# SCH_CANSAT-AD_K_2025-02-23.net
KiCad netlist of a schematic drawn in EasyEDA
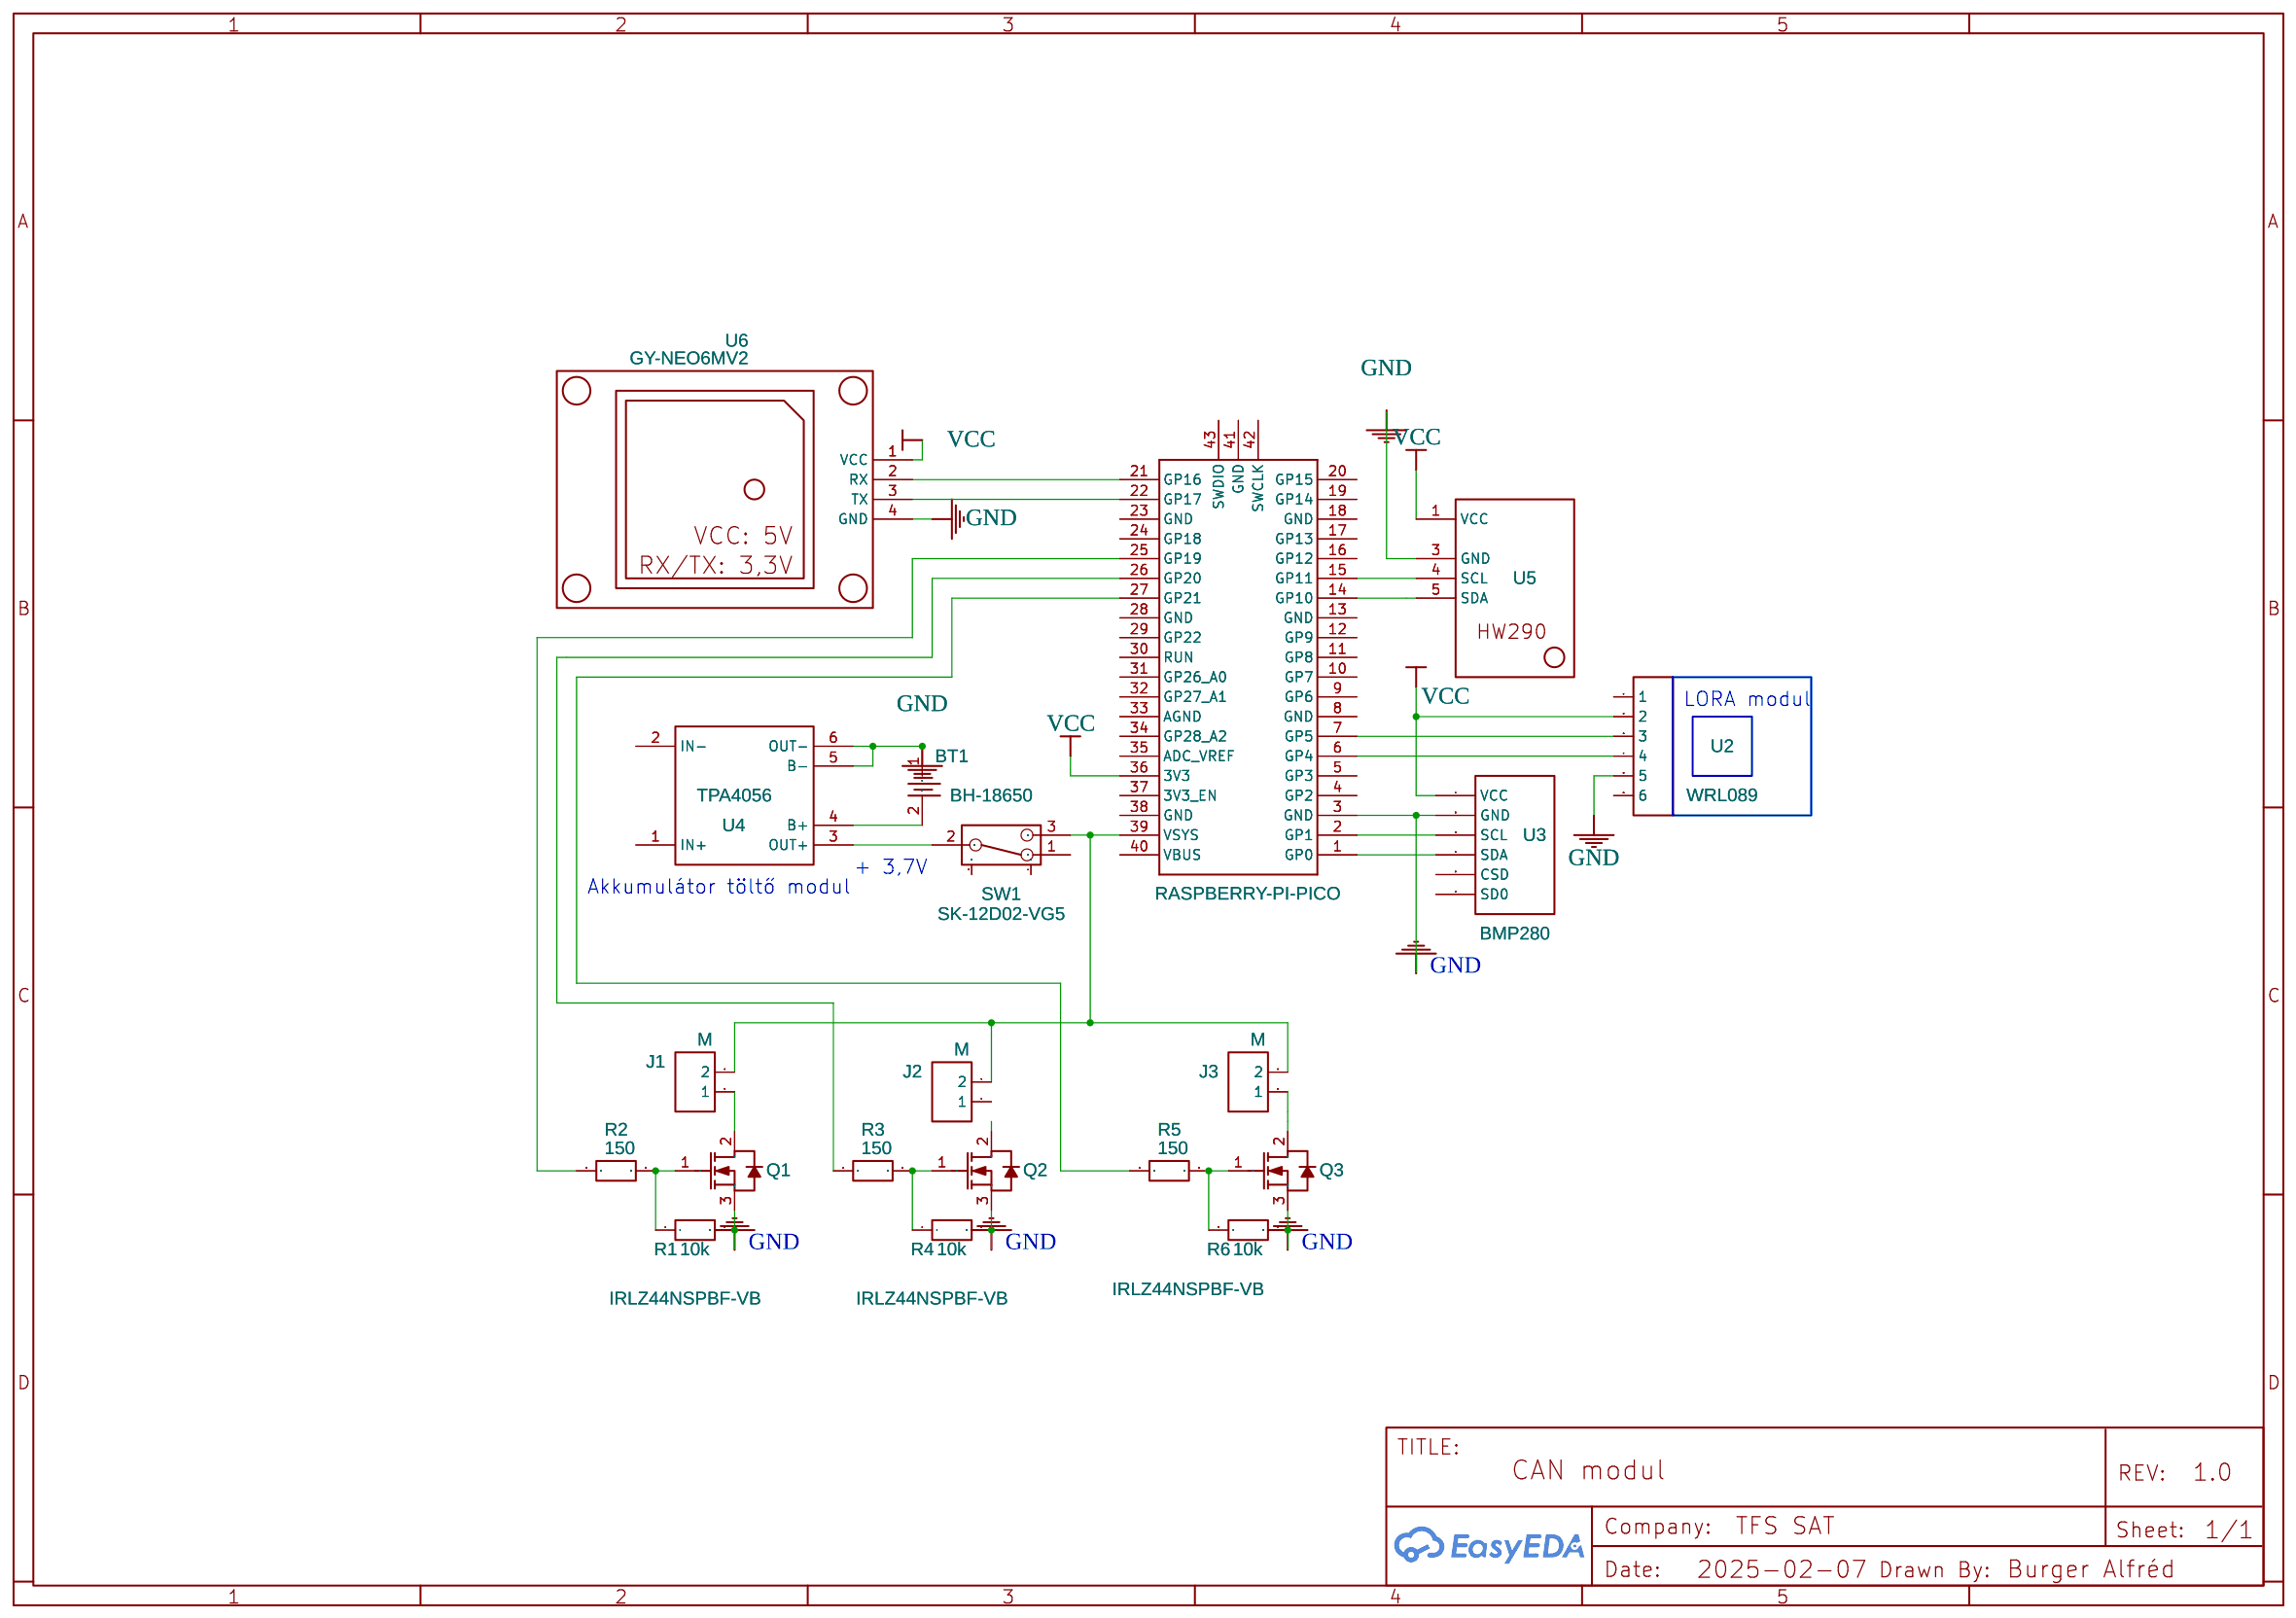
[diagram p0: schematic sheet]

(export (version "E")
  (design (tool "Eeschema 10.0.6"))
  (components
    (comp (ref "2")
      (value "RASPBERRY-PI-PICO")
      (fields (field (name "Manufacturer") "Raspberry Pi Foundation"))
      (libsource (lib "") (part "RASPBERRY-PI-PICO_TH/SMT"))
    )
    (comp (ref "BT1")
      (value "BH-18650")
      (fields
        (field (name "Manufacturer Part") "BH-18650-B1BA002")
        (field (name "Manufacturer") "MYOUNG(美阳)")
      )
      (libsource (lib "") (part "BH-18650-B1BA002"))
    )
    (comp (ref "J1") (value "M") (libsource (lib "") (part "HDR-M-2.54_1x2")))
    (comp (ref "J2") (value "M") (libsource (lib "") (part "HDR-M-2.54_1x2")))
    (comp (ref "J3") (value "M") (libsource (lib "") (part "HDR-M-2.54_1x2")))
    (comp (ref "Q1")
      (value "IRLZ44NSPBF-VB")
      (fields (field (name "Manufacturer") "VBsemi(微碧半导体)"))
      (libsource (lib "") (part "IRLZ44NSPBF-VB"))
    )
    (comp (ref "Q2")
      (value "IRLZ44NSPBF-VB")
      (fields (field (name "Manufacturer") "VBsemi(微碧半导体)"))
      (libsource (lib "") (part "IRLZ44NSPBF-VB"))
    )
    (comp (ref "Q3")
      (value "IRLZ44NSPBF-VB")
      (fields (field (name "Manufacturer") "VBsemi(微碧半导体)"))
      (libsource (lib "") (part "IRLZ44NSPBF-VB"))
    )
    (comp (ref "R1") (value "10k") (libsource (lib "") (part "R_0603_EU")))
    (comp (ref "R2") (value "150") (libsource (lib "") (part "R_0603_EU")))
    (comp (ref "R3") (value "150") (libsource (lib "") (part "R_0603_EU")))
    (comp (ref "R4") (value "10k") (libsource (lib "") (part "R_0603_EU")))
    (comp (ref "R5") (value "150") (libsource (lib "") (part "R_0603_EU")))
    (comp (ref "R6") (value "10k") (libsource (lib "") (part "R_0603_EU")))
    (comp (ref "SW1")
      (value "SK-12D02-VG5")
      (fields (field (name "Manufacturer") "Rectangular Connectors - Contacts"))
      (libsource (lib "") (part "SK-12D02-VG5"))
    )
    (comp (ref "U2") (value "WRL089") (libsource (lib "") (part "HDR-M-2.54_1x6")))
    (comp (ref "U3") (value "BMP280") (libsource (lib "") (part "BMP280")))
    (comp (ref "U4")
      (value "TPA4056")
      (fields (field (name "Manufacturer Part") "Djinn_sensor SchematicLib"))
      (libsource (lib "") (part "TPA4056"))
    )
    (comp (ref "U5") (value "HW290") (libsource (lib "") (part "10DOF-HW290-SYMBOL")))
    (comp (ref "U6") (value "GY-NEO6MV2") (libsource (lib "") (part "GY-GPS6MV2GPSModul")))
  )
  (nets
    (net (code "1") (name "GND") (class "Default")
      (node (ref "2") (pin "3") (pinfunction "GND_3") (pintype "bidirectional"))
      (node (ref "BT1") (pin "1") (pinfunction "1_1") (pintype "input"))
      (node (ref "Q1") (pin "3") (pinfunction "S_3") (pintype "unspecified"))
      (node (ref "Q2") (pin "3") (pinfunction "S_3") (pintype "unspecified"))
      (node (ref "Q3") (pin "3") (pinfunction "S_3") (pintype "unspecified"))
      (node (ref "R1") (pin "2") (pinfunction "2_2") (pintype "unspecified"))
      (node (ref "R4") (pin "2") (pinfunction "2_2") (pintype "unspecified"))
      (node (ref "R6") (pin "2") (pinfunction "2_2") (pintype "unspecified"))
      (node (ref "U2") (pin "5") (pinfunction "5_5") (pintype "input"))
      (node (ref "U3") (pin "6") (pinfunction "GND_6") (pintype "unspecified"))
      (node (ref "U4") (pin "5") (pinfunction "B-_5") (pintype "unspecified"))
      (node (ref "U4") (pin "6") (pinfunction "OUT-_6") (pintype "unspecified"))
      (node (ref "U5") (pin "3") (pinfunction "GND_3") (pintype "unspecified"))
      (node (ref "U6") (pin "4") (pinfunction "GND_4") (pintype "unspecified"))
    )
    (net (code "2") (name "Net-(2-GP0)") (class "Default")
      (node (ref "2") (pin "1") (pinfunction "GP0_1") (pintype "bidirectional"))
      (node (ref "U3") (pin "4") (pinfunction "SDA_4") (pintype "unspecified"))
    )
    (net (code "3") (name "Net-(2-GP1)") (class "Default")
      (node (ref "2") (pin "2") (pinfunction "GP1_2") (pintype "bidirectional"))
      (node (ref "U3") (pin "5") (pinfunction "SCL_5") (pintype "unspecified"))
    )
    (net (code "4") (name "Net-(2-GP4)") (class "Default")
      (node (ref "2") (pin "6") (pinfunction "GP4_6") (pintype "bidirectional"))
      (node (ref "U2") (pin "4") (pinfunction "4_4") (pintype "input"))
    )
    (net (code "5") (name "Net-(2-GP5)") (class "Default")
      (node (ref "2") (pin "7") (pinfunction "GP5_7") (pintype "bidirectional"))
      (node (ref "U2") (pin "3") (pinfunction "3_3") (pintype "input"))
    )
    (net (code "6") (name "Net-(2-GP10)") (class "Default")
      (node (ref "2") (pin "14") (pinfunction "GP10_14") (pintype "bidirectional"))
      (node (ref "U5") (pin "5") (pinfunction "SDA_5") (pintype "unspecified"))
    )
    (net (code "7") (name "Net-(2-GP11)") (class "Default")
      (node (ref "2") (pin "15") (pinfunction "GP11_15") (pintype "bidirectional"))
      (node (ref "U5") (pin "4") (pinfunction "SCL_4") (pintype "unspecified"))
    )
    (net (code "8") (name "Net-(2-GP16)") (class "Default")
      (node (ref "2") (pin "21") (pinfunction "GP16_21") (pintype "bidirectional"))
      (node (ref "U6") (pin "2") (pinfunction "RX_2") (pintype "unspecified"))
    )
    (net (code "9") (name "Net-(2-GP17)") (class "Default")
      (node (ref "2") (pin "22") (pinfunction "GP17_22") (pintype "bidirectional"))
      (node (ref "U6") (pin "3") (pinfunction "TX_3") (pintype "unspecified"))
    )
    (net (code "10") (name "Net-(2-GP19)") (class "Default")
      (node (ref "2") (pin "25") (pinfunction "GP19_25") (pintype "bidirectional"))
      (node (ref "R2") (pin "1") (pinfunction "1_1") (pintype "unspecified"))
    )
    (net (code "11") (name "Net-(2-GP20)") (class "Default")
      (node (ref "2") (pin "26") (pinfunction "GP20_26") (pintype "bidirectional"))
      (node (ref "R3") (pin "1") (pinfunction "1_1") (pintype "unspecified"))
    )
    (net (code "12") (name "Net-(2-GP21)") (class "Default")
      (node (ref "2") (pin "27") (pinfunction "GP21_27") (pintype "bidirectional"))
      (node (ref "R5") (pin "1") (pinfunction "1_1") (pintype "unspecified"))
    )
    (net (code "13") (name "Net-(2-VSYS)") (class "Default")
      (node (ref "2") (pin "39") (pinfunction "VSYS_39") (pintype "bidirectional"))
      (node (ref "J1") (pin "2") (pinfunction "2_2") (pintype "unspecified"))
      (node (ref "J2") (pin "2") (pinfunction "2_2") (pintype "unspecified"))
      (node (ref "J3") (pin "2") (pinfunction "2_2") (pintype "unspecified"))
      (node (ref "SW1") (pin "3") (pinfunction "3_3") (pintype "unspecified"))
    )
    (net (code "14") (name "Net-(Q1-D)") (class "Default")
      (node (ref "J1") (pin "1") (pinfunction "1_1") (pintype "unspecified"))
      (node (ref "Q1") (pin "2") (pinfunction "D_2") (pintype "unspecified"))
    )
    (net (code "15") (name "Net-(Q1-G)") (class "Default")
      (node (ref "Q1") (pin "1") (pinfunction "G_1") (pintype "unspecified"))
      (node (ref "R1") (pin "1") (pinfunction "1_1") (pintype "unspecified"))
      (node (ref "R2") (pin "2") (pinfunction "2_2") (pintype "unspecified"))
    )
    (net (code "16") (name "Net-(Q2-G)") (class "Default")
      (node (ref "Q2") (pin "1") (pinfunction "G_1") (pintype "unspecified"))
      (node (ref "R3") (pin "2") (pinfunction "2_2") (pintype "unspecified"))
      (node (ref "R4") (pin "1") (pinfunction "1_1") (pintype "unspecified"))
    )
    (net (code "17") (name "Net-(Q3-D)") (class "Default")
      (node (ref "J3") (pin "1") (pinfunction "1_1") (pintype "unspecified"))
      (node (ref "Q3") (pin "2") (pinfunction "D_2") (pintype "unspecified"))
    )
    (net (code "18") (name "Net-(Q3-G)") (class "Default")
      (node (ref "Q3") (pin "1") (pinfunction "G_1") (pintype "unspecified"))
      (node (ref "R5") (pin "2") (pinfunction "2_2") (pintype "unspecified"))
      (node (ref "R6") (pin "1") (pinfunction "1_1") (pintype "unspecified"))
    )
    (net (code "19") (name "Net-(U4-B+)") (class "Default")
      (node (ref "BT1") (pin "2") (pinfunction "2_2") (pintype "input"))
      (node (ref "U4") (pin "4") (pinfunction "B+_4") (pintype "unspecified"))
    )
    (net (code "20") (name "Net-(U4-OUT+)") (class "Default")
      (node (ref "SW1") (pin "2") (pinfunction "2_2") (pintype "unspecified"))
      (node (ref "U4") (pin "3") (pinfunction "OUT+_3") (pintype "unspecified"))
    )
    (net (code "21") (name "VCC") (class "Default")
      (node (ref "2") (pin "36") (pinfunction "3V3_36") (pintype "bidirectional"))
      (node (ref "U2") (pin "2") (pinfunction "2_2") (pintype "input"))
      (node (ref "U3") (pin "7") (pinfunction "VCC_7") (pintype "unspecified"))
      (node (ref "U5") (pin "1") (pinfunction "VCC_1") (pintype "unspecified"))
      (node (ref "U6") (pin "1") (pinfunction "VCC_1") (pintype "unspecified"))
    )
    (net (code "22") (name "unconnected-(2-3V3_EN-Pad37)") (class "Default")
      (node (ref "2") (pin "37") (pinfunction "3V3_EN_37") (pintype "bidirectional"))
    )
    (net (code "23") (name "unconnected-(2-ADC_VREF-Pad35)") (class "Default")
      (node (ref "2") (pin "35") (pinfunction "ADC_VREF_35") (pintype "bidirectional"))
    )
    (net (code "24") (name "unconnected-(2-AGND-Pad33)") (class "Default")
      (node (ref "2") (pin "33") (pinfunction "AGND_33") (pintype "bidirectional"))
    )
    (net (code "25") (name "unconnected-(2-GND-Pad8)") (class "Default")
      (node (ref "2") (pin "8") (pinfunction "GND_8") (pintype "bidirectional"))
    )
    (net (code "26") (name "unconnected-(2-GND-Pad13)") (class "Default")
      (node (ref "2") (pin "13") (pinfunction "GND_13") (pintype "bidirectional"))
    )
    (net (code "27") (name "unconnected-(2-GND-Pad18)") (class "Default")
      (node (ref "2") (pin "18") (pinfunction "GND_18") (pintype "bidirectional"))
    )
    (net (code "28") (name "unconnected-(2-GND-Pad23)") (class "Default")
      (node (ref "2") (pin "23") (pinfunction "GND_23") (pintype "bidirectional"))
    )
    (net (code "29") (name "unconnected-(2-GND-Pad28)") (class "Default")
      (node (ref "2") (pin "28") (pinfunction "GND_28") (pintype "bidirectional"))
    )
    (net (code "30") (name "unconnected-(2-GND-Pad38)") (class "Default")
      (node (ref "2") (pin "38") (pinfunction "GND_38") (pintype "bidirectional"))
    )
    (net (code "31") (name "unconnected-(2-GND-Pad41)") (class "Default")
      (node (ref "2") (pin "41") (pinfunction "GND_41") (pintype "bidirectional"))
    )
    (net (code "32") (name "unconnected-(2-GP2-Pad4)") (class "Default")
      (node (ref "2") (pin "4") (pinfunction "GP2_4") (pintype "bidirectional"))
    )
    (net (code "33") (name "unconnected-(2-GP3-Pad5)") (class "Default")
      (node (ref "2") (pin "5") (pinfunction "GP3_5") (pintype "bidirectional"))
    )
    (net (code "34") (name "unconnected-(2-GP6-Pad9)") (class "Default")
      (node (ref "2") (pin "9") (pinfunction "GP6_9") (pintype "bidirectional"))
    )
    (net (code "35") (name "unconnected-(2-GP7-Pad10)") (class "Default")
      (node (ref "2") (pin "10") (pinfunction "GP7_10") (pintype "bidirectional"))
    )
    (net (code "36") (name "unconnected-(2-GP8-Pad11)") (class "Default")
      (node (ref "2") (pin "11") (pinfunction "GP8_11") (pintype "bidirectional"))
    )
    (net (code "37") (name "unconnected-(2-GP9-Pad12)") (class "Default")
      (node (ref "2") (pin "12") (pinfunction "GP9_12") (pintype "bidirectional"))
    )
    (net (code "38") (name "unconnected-(2-GP12-Pad16)") (class "Default")
      (node (ref "2") (pin "16") (pinfunction "GP12_16") (pintype "bidirectional"))
    )
    (net (code "39") (name "unconnected-(2-GP13-Pad17)") (class "Default")
      (node (ref "2") (pin "17") (pinfunction "GP13_17") (pintype "bidirectional"))
    )
    (net (code "40") (name "unconnected-(2-GP14-Pad19)") (class "Default")
      (node (ref "2") (pin "19") (pinfunction "GP14_19") (pintype "bidirectional"))
    )
    (net (code "41") (name "unconnected-(2-GP15-Pad20)") (class "Default")
      (node (ref "2") (pin "20") (pinfunction "GP15_20") (pintype "bidirectional"))
    )
    (net (code "42") (name "unconnected-(2-GP18-Pad24)") (class "Default")
      (node (ref "2") (pin "24") (pinfunction "GP18_24") (pintype "bidirectional"))
    )
    (net (code "43") (name "unconnected-(2-GP22-Pad29)") (class "Default")
      (node (ref "2") (pin "29") (pinfunction "GP22_29") (pintype "bidirectional"))
    )
    (net (code "44") (name "unconnected-(2-GP26_A0-Pad31)") (class "Default")
      (node (ref "2") (pin "31") (pinfunction "GP26_A0_31") (pintype "bidirectional"))
    )
    (net (code "45") (name "unconnected-(2-GP27_A1-Pad32)") (class "Default")
      (node (ref "2") (pin "32") (pinfunction "GP27_A1_32") (pintype "bidirectional"))
    )
    (net (code "46") (name "unconnected-(2-GP28_A2-Pad34)") (class "Default")
      (node (ref "2") (pin "34") (pinfunction "GP28_A2_34") (pintype "bidirectional"))
    )
    (net (code "47") (name "unconnected-(2-RUN-Pad30)") (class "Default")
      (node (ref "2") (pin "30") (pinfunction "RUN_30") (pintype "bidirectional"))
    )
    (net (code "48") (name "unconnected-(2-SWCLK-Pad42)") (class "Default")
      (node (ref "2") (pin "42") (pinfunction "SWCLK_42") (pintype "bidirectional"))
    )
    (net (code "49") (name "unconnected-(2-SWDIO-Pad43)") (class "Default")
      (node (ref "2") (pin "43") (pinfunction "SWDIO_43") (pintype "bidirectional"))
    )
    (net (code "50") (name "unconnected-(2-VBUS-Pad40)") (class "Default")
      (node (ref "2") (pin "40") (pinfunction "VBUS_40") (pintype "bidirectional"))
    )
    (net (code "51") (name "unconnected-(J2-Pad1)") (class "Default")
      (node (ref "J2") (pin "1") (pinfunction "1_1") (pintype "unspecified"))
    )
    (net (code "52") (name "unconnected-(Q2-D-Pad2)") (class "Default")
      (node (ref "Q2") (pin "2") (pinfunction "D_2") (pintype "unspecified"))
    )
    (net (code "53") (name "unconnected-(SW1-Pad1)") (class "Default")
      (node (ref "SW1") (pin "1") (pinfunction "1_1") (pintype "unspecified"))
    )
    (net (code "54") (name "unconnected-(SW1-Pad4)") (class "Default")
      (node (ref "SW1") (pin "4") (pinfunction "4_4") (pintype "unspecified"))
    )
    (net (code "55") (name "unconnected-(SW1-Pad5)") (class "Default")
      (node (ref "SW1") (pin "5") (pinfunction "5_5") (pintype "unspecified"))
    )
    (net (code "56") (name "unconnected-(U2-Pad1)") (class "Default")
      (node (ref "U2") (pin "1") (pinfunction "1_1") (pintype "input"))
    )
    (net (code "57") (name "unconnected-(U2-Pad6)") (class "Default")
      (node (ref "U2") (pin "6") (pinfunction "6_6") (pintype "input"))
    )
    (net (code "58") (name "unconnected-(U3-CSD-Pad3)") (class "Default")
      (node (ref "U3") (pin "3") (pinfunction "CSD_3") (pintype "unspecified"))
    )
    (net (code "59") (name "unconnected-(U3-SD0-Pad2)") (class "Default")
      (node (ref "U3") (pin "2") (pinfunction "SD0_2") (pintype "unspecified"))
    )
    (net (code "60") (name "unconnected-(U4-IN+-Pad1)") (class "Default")
      (node (ref "U4") (pin "1") (pinfunction "IN+_1") (pintype "unspecified"))
    )
    (net (code "61") (name "unconnected-(U4-IN--Pad2)") (class "Default")
      (node (ref "U4") (pin "2") (pinfunction "IN-_2") (pintype "unspecified"))
    )
  )
)
